# OPENMV3.net
KiCad netlist of a schematic drawn in Altium Designer
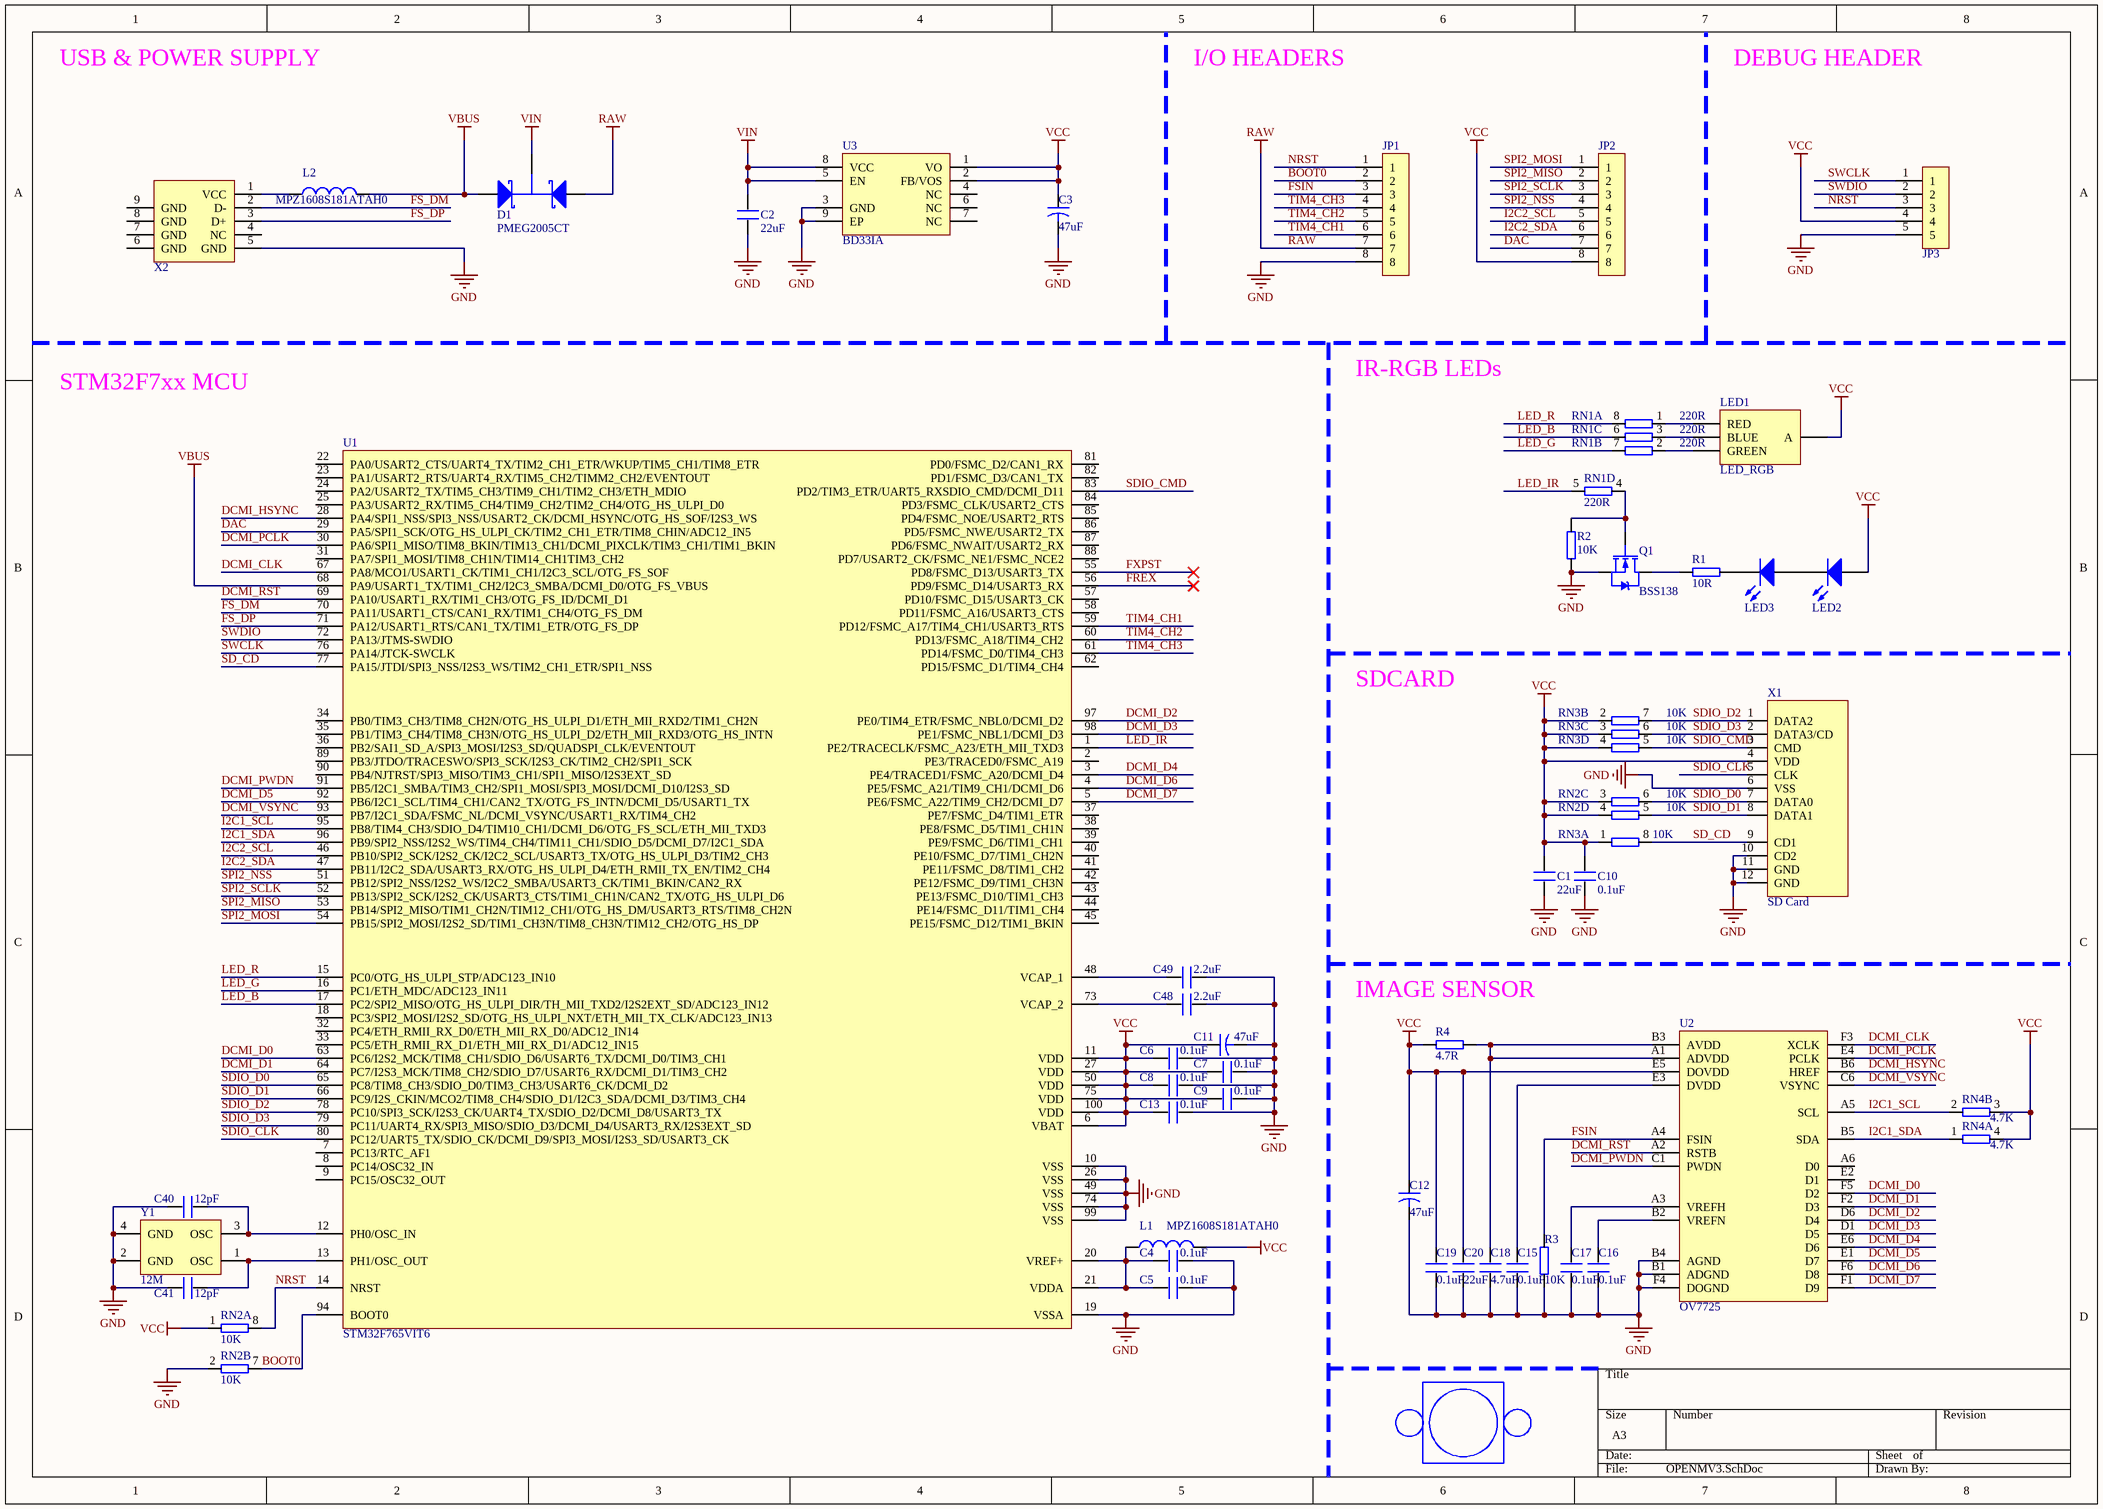
[diagram p0: OPENMV3.SchDoc]

(export (version "E")
  (design (tool "Eeschema 10.0.6"))
  (components
    (comp (ref "C1")
      (value "22uF")
      (footprint "C0603")
      (fields (field (name "Comment") "CAP"))
      (libsource (lib "MyLib") (part "C"))
    )
    (comp (ref "C2")
      (value "22uF")
      (footprint "C0603")
      (fields (field (name "Comment") "CAP"))
      (libsource (lib "MyLib") (part "C"))
    )
    (comp (ref "C3")
      (value "47uF")
      (footprint "CAP-A")
      (fields (field (name "Comment") "CAP"))
      (libsource (lib "MyLib") (part "CAP-B"))
    )
    (comp (ref "C4")
      (value "0.1uF")
      (footprint "C0603")
      (fields (field (name "Comment") "CAP"))
      (libsource (lib "MyLib") (part "C"))
    )
    (comp (ref "C5")
      (value "0.1uF")
      (footprint "C0603")
      (fields (field (name "Comment") "CAP"))
      (libsource (lib "MyLib") (part "C"))
    )
    (comp (ref "C6")
      (value "0.1uF")
      (footprint "C0603")
      (fields (field (name "Comment") "CAP"))
      (libsource (lib "MyLib") (part "C"))
    )
    (comp (ref "C7")
      (value "0.1uF")
      (footprint "C0603")
      (fields (field (name "Comment") "CAP"))
      (libsource (lib "MyLib") (part "C"))
    )
    (comp (ref "C8")
      (value "0.1uF")
      (footprint "C0603")
      (fields (field (name "Comment") "CAP"))
      (libsource (lib "MyLib") (part "C"))
    )
    (comp (ref "C9")
      (value "0.1uF")
      (footprint "C0603")
      (fields (field (name "Comment") "CAP"))
      (libsource (lib "MyLib") (part "C"))
    )
    (comp (ref "C10")
      (value "0.1uF")
      (footprint "C0603")
      (fields (field (name "Comment") "CAP"))
      (libsource (lib "MyLib") (part "C"))
    )
    (comp (ref "C11")
      (value "47uF")
      (footprint "CAP-A")
      (fields (field (name "Comment") "CAP"))
      (libsource (lib "MyLib") (part "CAP-B"))
    )
    (comp (ref "C12")
      (value "47uF")
      (footprint "CAP-A")
      (fields (field (name "Comment") "CAP"))
      (libsource (lib "MyLib") (part "CAP-B"))
    )
    (comp (ref "C13")
      (value "0.1uF")
      (footprint "C0603")
      (fields (field (name "Comment") "CAP"))
      (libsource (lib "MyLib") (part "C"))
    )
    (comp (ref "C15")
      (value "0.1uF")
      (footprint "C0603")
      (fields (field (name "Comment") "CAP"))
      (libsource (lib "MyLib") (part "C"))
    )
    (comp (ref "C16")
      (value "0.1uF")
      (footprint "C0603")
      (fields (field (name "Comment") "CAP"))
      (libsource (lib "MyLib") (part "C"))
    )
    (comp (ref "C17")
      (value "0.1uF")
      (footprint "C0603")
      (fields (field (name "Comment") "CAP"))
      (libsource (lib "MyLib") (part "C"))
    )
    (comp (ref "C18")
      (value "4.7uF")
      (footprint "C0603")
      (fields (field (name "Comment") "CAP"))
      (libsource (lib "MyLib") (part "C"))
    )
    (comp (ref "C19")
      (value "0.1uF")
      (footprint "C0603")
      (fields (field (name "Comment") "CAP"))
      (libsource (lib "MyLib") (part "C"))
    )
    (comp (ref "C20")
      (value "22uF")
      (footprint "C0603")
      (fields (field (name "Comment") "CAP"))
      (libsource (lib "MyLib") (part "C"))
    )
    (comp (ref "C40")
      (value "12pF")
      (footprint "C0603")
      (fields (field (name "Comment") "CAP"))
      (libsource (lib "MyLib") (part "C"))
    )
    (comp (ref "C41")
      (value "12pF")
      (footprint "C0603")
      (fields (field (name "Comment") "CAP"))
      (libsource (lib "MyLib") (part "C"))
    )
    (comp (ref "C48")
      (value "2.2uF")
      (footprint "C0603")
      (fields (field (name "Comment") "CAP"))
      (libsource (lib "MyLib") (part "C"))
    )
    (comp (ref "C49")
      (value "2.2uF")
      (footprint "C0603")
      (fields (field (name "Comment") "CAP"))
      (libsource (lib "MyLib") (part "C"))
    )
    (comp (ref "D1") (value "PMEG2005CT") (footprint "SOT-23") (libsource (lib "MyLib") (part "D_Double")))
    (comp (ref "JP1")
      (value "HEADER1*8")
      (footprint "HEADER1*8_oct")
      (libsource (lib "MyLib") (part "HEADER1*8"))
    )
    (comp (ref "JP2")
      (value "HEADER1*8")
      (footprint "HEADER1*8_oct")
      (libsource (lib "MyLib") (part "HEADER1*8"))
    )
    (comp (ref "JP3")
      (value "HEADER1*5")
      (footprint "HEADER1*5_oct")
      (libsource (lib "MyLib") (part "HEADER1*5"))
    )
    (comp (ref "L1")
      (value "MPZ1608S181ATAH0")
      (footprint "R0603")
      (fields (field (name "Comment") "Inductance"))
      (libsource (lib "MyLib") (part "L"))
    )
    (comp (ref "L2")
      (value "MPZ1608S181ATAH0")
      (footprint "R0603")
      (fields (field (name "Comment") "Inductance"))
      (libsource (lib "MyLib") (part "L"))
    )
    (comp (ref "LED1")
      (value "LED_RGB")
      (footprint "LED_RGB_3528")
      (libsource (lib "MyLib") (part "LED_RGB"))
    )
    (comp (ref "LED2") (value "LED") (footprint "LED1206") (libsource (lib "MyLib") (part "LED")))
    (comp (ref "LED3") (value "LED") (footprint "LED1206") (libsource (lib "MyLib") (part "LED")))
    (comp (ref "P0")
      (value "CameraLens")
      (footprint "CamLens_M12-2016")
      (libsource (lib "MyLib") (part "CameraLens"))
    )
    (comp (ref "Q1") (value "BSS138") (footprint "sot-23") (libsource (lib "MyLib") (part "AO3402")))
    (comp (ref "R1")
      (value "10R")
      (footprint "R0603")
      (fields (field (name "Comment") "Resistor"))
      (libsource (lib "MyLib") (part "R"))
    )
    (comp (ref "R2")
      (value "10K")
      (footprint "R0603")
      (fields (field (name "Comment") "Resistor"))
      (libsource (lib "MyLib") (part "R"))
    )
    (comp (ref "R3")
      (value "10K")
      (footprint "R0603")
      (fields (field (name "Comment") "Resistor"))
      (libsource (lib "MyLib") (part "R"))
    )
    (comp (ref "R4")
      (value "4.7R")
      (footprint "R0603")
      (fields (field (name "Comment") "Resistor"))
      (libsource (lib "MyLib") (part "R"))
    )
    (comp (ref "RN1")
      (value "220R")
      (footprint "R0603_x4")
      (fields (field (name "Comment") "Res"))
      (libsource (lib "MyLib") (part "RES-Pack4"))
    )
    (comp (ref "RN2")
      (value "10K")
      (footprint "R0603_x4")
      (fields (field (name "Comment") "Res"))
      (libsource (lib "MyLib") (part "RES-Pack4"))
    )
    (comp (ref "RN3")
      (value "10K")
      (footprint "R0603_x4")
      (fields (field (name "Comment") "Res"))
      (libsource (lib "MyLib") (part "RES-Pack4"))
    )
    (comp (ref "RN4")
      (value "4.7K")
      (footprint "R0603_x2")
      (fields (field (name "Comment") "Res"))
      (libsource (lib "MyLib") (part "RES-Pack2"))
    )
    (comp (ref "U1")
      (value "STM32F765VIT6")
      (footprint "LQFP100")
      (libsource (lib "MyLib") (part "STM32F765VIT6"))
    )
    (comp (ref "U2")
      (value "OV7725")
      (footprint "BGA28C80P6X6_535X535X96")
      (libsource (lib "MyLib") (part "OV7725"))
    )
    (comp (ref "U3") (value "BD33IA") (footprint "SOIC8-HS") (libsource (lib "MyLib") (part "BD33IA")))
    (comp (ref "X1") (value "SD Card") (footprint "SD_Slot") (libsource (lib "MyLib") (part "SD_Slot")))
    (comp (ref "X2") (value "USB") (footprint "MicroUSB_5P_2h") (libsource (lib "MyLib") (part "USB")))
    (comp (ref "Y1")
      (value "12M")
      (footprint "XTAL-3225")
      (fields (field (name "Comment") "Crystal"))
      (libsource (lib "MyLib") (part "无源晶振"))
    )
  )
  (nets
    (net (code "1") (name "/BOOT0") (class "Default")
      (node (ref "JP1") (pin "2") (pinfunction "2_2") (pintype "passive"))
      (node (ref "RN2") (pin "7") (pintype "passive"))
      (node (ref "U1") (pin "94") (pinfunction "BOOT0_94") (pintype "passive"))
    )
    (net (code "2") (name "/DAC") (class "Default")
      (node (ref "JP2") (pin "7") (pinfunction "7_7") (pintype "passive"))
      (node (ref "U1") (pin "29") (pinfunction "PA5/SPI1_SCK/OTG_HS_ULPI_CK/TIM2_CH1_ETR/TIM8_CHIN/ADC12_IN5_29") (pintype "passive"))
    )
    (net (code "3") (name "/DCMI_CLK") (class "Default")
      (node (ref "U1") (pin "67") (pinfunction "PA8/MCO1/USART1_CK/TIM1_CH1/I2C3_SCL/OTG_FS_SOF_67") (pintype "passive"))
      (node (ref "U2") (pin "F3") (pinfunction "XCLK_F3") (pintype "passive"))
    )
    (net (code "4") (name "/DCMI_D0") (class "Default")
      (node (ref "U1") (pin "63") (pinfunction "PC6/I2S2_MCK/TIM8_CH1/SDIO_D6/USART6_TX/DCMI_D0/TIM3_CH1_63") (pintype "passive"))
      (node (ref "U2") (pin "F5") (pinfunction "D2_F5") (pintype "passive"))
    )
    (net (code "5") (name "/DCMI_D1") (class "Default")
      (node (ref "U1") (pin "64") (pinfunction "PC7/I2S3_MCK/TIM8_CH2/SDIO_D7/USART6_RX/DCMI_D1/TIM3_CH2_64") (pintype "passive"))
      (node (ref "U2") (pin "F2") (pinfunction "D3_F2") (pintype "passive"))
    )
    (net (code "6") (name "/DCMI_D2") (class "Default")
      (node (ref "U1") (pin "97") (pinfunction "PE0/TIM4_ETR/FSMC_NBL0/DCMI_D2_97") (pintype "passive"))
      (node (ref "U2") (pin "D6") (pinfunction "D4_D6") (pintype "passive"))
    )
    (net (code "7") (name "/DCMI_D3") (class "Default")
      (node (ref "U1") (pin "98") (pinfunction "PE1/FSMC_NBL1/DCMI_D3_98") (pintype "passive"))
      (node (ref "U2") (pin "D1") (pinfunction "D5_D1") (pintype "passive"))
    )
    (net (code "8") (name "/DCMI_D4") (class "Default")
      (node (ref "U1") (pin "3") (pinfunction "PE4/TRACED1/FSMC_A20/DCMI_D4_3") (pintype "passive"))
      (node (ref "U2") (pin "E6") (pinfunction "D6_E6") (pintype "passive"))
    )
    (net (code "9") (name "/DCMI_D5") (class "Default")
      (node (ref "U1") (pin "92") (pinfunction "PB6/I2C1_SCL/TIM4_CH1/CAN2_TX/OTG_FS_INTN/DCMI_D5/USART1_TX_92") (pintype "passive"))
      (node (ref "U2") (pin "E1") (pinfunction "D7_E1") (pintype "passive"))
    )
    (net (code "10") (name "/DCMI_D6") (class "Default")
      (node (ref "U1") (pin "4") (pinfunction "PE5/FSMC_A21/TIM9_CH1/DCMI_D6_4") (pintype "passive"))
      (node (ref "U2") (pin "F6") (pinfunction "D8_F6") (pintype "passive"))
    )
    (net (code "11") (name "/DCMI_D7") (class "Default")
      (node (ref "U1") (pin "5") (pinfunction "PE6/FSMC_A22/TIM9_CH2/DCMI_D7_5") (pintype "passive"))
      (node (ref "U2") (pin "F1") (pinfunction "D9_F1") (pintype "passive"))
    )
    (net (code "12") (name "/DCMI_HSYNC") (class "Default")
      (node (ref "U1") (pin "28") (pinfunction "PA4/SPI1_NSS/SPI3_NSS/USART2_CK/DCMI_HSYNC/OTG_HS_SOF/I2S3_WS_28") (pintype "passive"))
      (node (ref "U2") (pin "B6") (pinfunction "HREF_B6") (pintype "passive"))
    )
    (net (code "13") (name "/DCMI_PCLK") (class "Default")
      (node (ref "U1") (pin "30") (pinfunction "PA6/SPI1_MISO/TIM8_BKIN/TIM13_CH1/DCMI_PIXCLK/TIM3_CH1/TIM1_BKIN_30") (pintype "passive"))
      (node (ref "U2") (pin "E4") (pinfunction "PCLK_E4") (pintype "passive"))
    )
    (net (code "14") (name "/DCMI_PWDN") (class "Default")
      (node (ref "U1") (pin "91") (pinfunction "PB5/I2C1_SMBA/TIM3_CH2/SPI1_MOSI/SPI3_MOSI/DCMI_D10/I2S3_SD_91") (pintype "passive"))
      (node (ref "U2") (pin "C1") (pinfunction "PWDN_C1") (pintype "passive"))
    )
    (net (code "15") (name "/DCMI_RST") (class "Default")
      (node (ref "U1") (pin "69") (pinfunction "PA10/USART1_RX/TIM1_CH3/OTG_FS_ID/DCMI_D1_69") (pintype "passive"))
      (node (ref "U2") (pin "A2") (pinfunction "RSTB_A2") (pintype "passive"))
    )
    (net (code "16") (name "/DCMI_VSYNC") (class "Default")
      (node (ref "U1") (pin "93") (pinfunction "PB7/I2C1_SDA/FSMC_NL/DCMI_VSYNC/USART1_RX/TIM4_CH2_93") (pintype "passive"))
      (node (ref "U2") (pin "C6") (pinfunction "VSYNC_C6") (pintype "passive"))
    )
    (net (code "17") (name "/FREX") (class "Default")
      (node (ref "U1") (pin "56") (pinfunction "PD9/FSMC_D14/USART3_RX_56") (pintype "passive+no_connect"))
    )
    (net (code "18") (name "/FSIN") (class "Default")
      (node (ref "JP1") (pin "3") (pinfunction "3_3") (pintype "passive"))
      (node (ref "R3") (pin "2") (pintype "passive"))
      (node (ref "U2") (pin "A4") (pinfunction "FSIN_A4") (pintype "passive"))
    )
    (net (code "19") (name "/FS_DM") (class "Default")
      (node (ref "U1") (pin "70") (pinfunction "PA11/USART1_CTS/CAN1_RX/TIM1_CH4/OTG_FS_DM_70") (pintype "passive"))
      (node (ref "X2") (pin "2") (pinfunction "D-_2") (pintype "passive"))
    )
    (net (code "20") (name "/FS_DP") (class "Default")
      (node (ref "U1") (pin "71") (pinfunction "PA12/USART1_RTS/CAN1_TX/TIM1_ETR/OTG_FS_DP_71") (pintype "passive"))
      (node (ref "X2") (pin "3") (pinfunction "D+_3") (pintype "passive"))
    )
    (net (code "21") (name "/FXPST") (class "Default")
      (node (ref "U1") (pin "55") (pinfunction "PD8/FSMC_D13/USART3_TX_55") (pintype "passive+no_connect"))
    )
    (net (code "22") (name "/I2C1_SCL") (class "Default")
      (node (ref "RN4") (pin "2") (pintype "passive"))
      (node (ref "U1") (pin "95") (pinfunction "PB8/TIM4_CH3/SDIO_D4/TIM10_CH1/DCMI_D6/OTG_FS_SCL/ETH_MII_TXD3_95") (pintype "passive"))
      (node (ref "U2") (pin "A5") (pinfunction "SCL_A5") (pintype "passive"))
    )
    (net (code "23") (name "/I2C1_SDA") (class "Default")
      (node (ref "RN4") (pin "1") (pinfunction "1_1") (pintype "passive"))
      (node (ref "U1") (pin "96") (pinfunction "PB9/SPI2_NSS/I2S2_WS/TIM4_CH4/TIM11_CH1/SDIO_D5/DCMI_D7/I2C1_SDA_96") (pintype "passive"))
      (node (ref "U2") (pin "B5") (pinfunction "SDA_B5") (pintype "passive"))
    )
    (net (code "24") (name "/I2C2_SCL") (class "Default")
      (node (ref "JP2") (pin "5") (pinfunction "5_5") (pintype "passive"))
      (node (ref "U1") (pin "46") (pinfunction "PB10/SPI2_SCK/I2S2_CK/I2C2_SCL/USART3_TX/OTG_HS_ULPI_D3/TIM2_CH3_46") (pintype "passive"))
    )
    (net (code "25") (name "/I2C2_SDA") (class "Default")
      (node (ref "JP2") (pin "6") (pinfunction "6_6") (pintype "passive"))
      (node (ref "U1") (pin "47") (pinfunction "PB11/I2C2_SDA/USART3_RX/OTG_HS_ULPI_D4/ETH_RMII_TX_EN/TIM2_CH4_47") (pintype "passive"))
    )
    (net (code "26") (name "/LED_B") (class "Default")
      (node (ref "RN1") (pin "6") (pintype "passive"))
      (node (ref "U1") (pin "17") (pinfunction "PC2/SPI2_MISO/OTG_HS_ULPI_DIR/TH_MII_TXD2/I2S2EXT_SD/ADC123_IN12_17") (pintype "passive"))
    )
    (net (code "27") (name "/LED_G") (class "Default")
      (node (ref "RN1") (pin "7") (pintype "passive"))
      (node (ref "U1") (pin "16") (pinfunction "PC1/ETH_MDC/ADC123_IN11_16") (pintype "passive"))
    )
    (net (code "28") (name "/LED_IR") (class "Default")
      (node (ref "RN1") (pin "5") (pintype "passive"))
      (node (ref "U1") (pin "1") (pinfunction "PE2/TRACECLK/FSMC_A23/ETH_MII_TXD3_1") (pintype "passive"))
    )
    (net (code "29") (name "/LED_R") (class "Default")
      (node (ref "RN1") (pin "8") (pinfunction "8_8") (pintype "passive"))
      (node (ref "U1") (pin "15") (pinfunction "PC0/OTG_HS_ULPI_STP/ADC123_IN10_15") (pintype "passive"))
    )
    (net (code "30") (name "/NRST") (class "Default")
      (node (ref "JP1") (pin "1") (pinfunction "1_1") (pintype "passive"))
      (node (ref "JP3") (pin "3") (pinfunction "3_3") (pintype "passive"))
      (node (ref "RN2") (pin "8") (pinfunction "8_8") (pintype "passive"))
      (node (ref "U1") (pin "14") (pinfunction "NRST_14") (pintype "passive"))
    )
    (net (code "31") (name "/SDIO_CLK") (class "Default")
      (node (ref "U1") (pin "80") (pinfunction "PC12/UART5_TX/SDIO_CK/DCMI_D9/SPI3_MOSI/I2S3_SD/USART3_CK_80") (pintype "passive"))
      (node (ref "X1") (pin "5") (pinfunction "CLK_5") (pintype "passive"))
    )
    (net (code "32") (name "/SDIO_CMD") (class "Default")
      (node (ref "RN3") (pin "5") (pintype "passive"))
      (node (ref "U1") (pin "83") (pinfunction "PD2/TIM3_ETR/UART5_RXSDIO_CMD/DCMI_D11_83") (pintype "passive"))
      (node (ref "X1") (pin "3") (pinfunction "CMD_3") (pintype "passive"))
    )
    (net (code "33") (name "/SDIO_D0") (class "Default")
      (node (ref "RN2") (pin "6") (pintype "passive"))
      (node (ref "U1") (pin "65") (pinfunction "PC8/TIM8_CH3/SDIO_D0/TIM3_CH3/USART6_CK/DCMI_D2_65") (pintype "passive"))
      (node (ref "X1") (pin "7") (pinfunction "DATA0_7") (pintype "passive"))
    )
    (net (code "34") (name "/SDIO_D1") (class "Default")
      (node (ref "RN2") (pin "5") (pintype "passive"))
      (node (ref "U1") (pin "66") (pinfunction "PC9/I2S_CKIN/MCO2/TIM8_CH4/SDIO_D1/I2C3_SDA/DCMI_D3/TIM3_CH4_66") (pintype "passive"))
      (node (ref "X1") (pin "8") (pinfunction "DATA1_8") (pintype "passive"))
    )
    (net (code "35") (name "/SDIO_D2") (class "Default")
      (node (ref "RN3") (pin "7") (pintype "passive"))
      (node (ref "U1") (pin "78") (pinfunction "PC10/SPI3_SCK/I2S3_CK/UART4_TX/SDIO_D2/DCMI_D8/USART3_TX_78") (pintype "passive"))
      (node (ref "X1") (pin "1") (pinfunction "DATA2_1") (pintype "passive"))
    )
    (net (code "36") (name "/SDIO_D3") (class "Default")
      (node (ref "RN3") (pin "6") (pintype "passive"))
      (node (ref "U1") (pin "79") (pinfunction "PC11/UART4_RX/SPI3_MISO/SDIO_D3/DCMI_D4/USART3_RX/I2S3EXT_SD_79") (pintype "passive"))
      (node (ref "X1") (pin "2") (pinfunction "DATA3/CD_2") (pintype "passive"))
    )
    (net (code "37") (name "/SD_CD") (class "Default")
      (node (ref "RN3") (pin "8") (pinfunction "8_8") (pintype "passive"))
      (node (ref "U1") (pin "77") (pinfunction "PA15/JTDI/SPI3_NSS/I2S3_WS/TIM2_CH1_ETR/SPI1_NSS_77") (pintype "passive"))
      (node (ref "X1") (pin "9") (pinfunction "CD1_9") (pintype "passive"))
    )
    (net (code "38") (name "/SPI2_MISO") (class "Default")
      (node (ref "JP2") (pin "2") (pinfunction "2_2") (pintype "passive"))
      (node (ref "U1") (pin "53") (pinfunction "PB14/SPI2_MISO/TIM1_CH2N/TIM12_CH1/OTG_HS_DM/USART3_RTS/TIM8_CH2N_53") (pintype "passive"))
    )
    (net (code "39") (name "/SPI2_MOSI") (class "Default")
      (node (ref "JP2") (pin "1") (pinfunction "1_1") (pintype "passive"))
      (node (ref "U1") (pin "54") (pinfunction "PB15/SPI2_MOSI/I2S2_SD/TIM1_CH3N/TIM8_CH3N/TIM12_CH2/OTG_HS_DP_54") (pintype "passive"))
    )
    (net (code "40") (name "/SPI2_NSS") (class "Default")
      (node (ref "JP2") (pin "4") (pinfunction "4_4") (pintype "passive"))
      (node (ref "U1") (pin "51") (pinfunction "PB12/SPI2_NSS/I2S2_WS/I2C2_SMBA/USART3_CK/TIM1_BKIN/CAN2_RX_51") (pintype "passive"))
    )
    (net (code "41") (name "/SPI2_SCLK") (class "Default")
      (node (ref "JP2") (pin "3") (pinfunction "3_3") (pintype "passive"))
      (node (ref "U1") (pin "52") (pinfunction "PB13/SPI2_SCK/I2S2_CK/USART3_CTS/TIM1_CH1N/CAN2_TX/OTG_HS_ULPI_D6_52") (pintype "passive"))
    )
    (net (code "42") (name "/SWCLK") (class "Default")
      (node (ref "JP3") (pin "1") (pinfunction "1_1") (pintype "passive"))
      (node (ref "U1") (pin "76") (pinfunction "PA14/JTCK-SWCLK_76") (pintype "passive"))
    )
    (net (code "43") (name "/SWDIO") (class "Default")
      (node (ref "JP3") (pin "2") (pinfunction "2_2") (pintype "passive"))
      (node (ref "U1") (pin "72") (pinfunction "PA13/JTMS-SWDIO_72") (pintype "passive"))
    )
    (net (code "44") (name "/TIM4_CH1") (class "Default")
      (node (ref "JP1") (pin "6") (pinfunction "6_6") (pintype "passive"))
      (node (ref "U1") (pin "59") (pinfunction "PD12/FSMC_A17/TIM4_CH1/USART3_RTS_59") (pintype "passive"))
    )
    (net (code "45") (name "/TIM4_CH2") (class "Default")
      (node (ref "JP1") (pin "5") (pinfunction "5_5") (pintype "passive"))
      (node (ref "U1") (pin "60") (pinfunction "PD13/FSMC_A18/TIM4_CH2_60") (pintype "passive"))
    )
    (net (code "46") (name "/TIM4_CH3") (class "Default")
      (node (ref "JP1") (pin "4") (pinfunction "4_4") (pintype "passive"))
      (node (ref "U1") (pin "61") (pinfunction "PD14/FSMC_D0/TIM4_CH3_61") (pintype "passive"))
    )
    (net (code "47") (name "GND") (class "Default")
      (node (ref "C1") (pin "1") (pintype "passive"))
      (node (ref "C10") (pin "1") (pintype "passive"))
      (node (ref "C11") (pin "1") (pinfunction "1_1") (pintype "passive"))
      (node (ref "C12") (pin "1") (pinfunction "1_1") (pintype "passive"))
      (node (ref "C13") (pin "2") (pintype "passive"))
      (node (ref "C15") (pin "1") (pintype "passive"))
      (node (ref "C16") (pin "1") (pintype "passive"))
      (node (ref "C17") (pin "1") (pintype "passive"))
      (node (ref "C18") (pin "1") (pintype "passive"))
      (node (ref "C19") (pin "1") (pintype "passive"))
      (node (ref "C2") (pin "1") (pintype "passive"))
      (node (ref "C20") (pin "1") (pintype "passive"))
      (node (ref "C3") (pin "1") (pinfunction "1_1") (pintype "passive"))
      (node (ref "C4") (pin "2") (pintype "passive"))
      (node (ref "C40") (pin "2") (pintype "passive"))
      (node (ref "C41") (pin "2") (pintype "passive"))
      (node (ref "C48") (pin "1") (pintype "passive"))
      (node (ref "C49") (pin "1") (pintype "passive"))
      (node (ref "C5") (pin "2") (pintype "passive"))
      (node (ref "C6") (pin "2") (pintype "passive"))
      (node (ref "C7") (pin "2") (pintype "passive"))
      (node (ref "C8") (pin "2") (pintype "passive"))
      (node (ref "C9") (pin "2") (pintype "passive"))
      (node (ref "JP1") (pin "8") (pinfunction "8_8") (pintype "passive"))
      (node (ref "JP3") (pin "5") (pinfunction "5_5") (pintype "passive"))
      (node (ref "Q1") (pin "2") (pinfunction "S_2") (pintype "passive"))
      (node (ref "R2") (pin "1") (pintype "passive"))
      (node (ref "R3") (pin "1") (pintype "passive"))
      (node (ref "RN2") (pin "2") (pintype "passive"))
      (node (ref "U1") (pin "10") (pinfunction "VSS_10") (pintype "passive"))
      (node (ref "U1") (pin "19") (pinfunction "VSSA_19") (pintype "passive"))
      (node (ref "U1") (pin "26") (pinfunction "VSS_26") (pintype "passive"))
      (node (ref "U1") (pin "49") (pinfunction "VSS_49") (pintype "passive"))
      (node (ref "U1") (pin "74") (pinfunction "VSS_74") (pintype "passive"))
      (node (ref "U1") (pin "99") (pinfunction "VSS_99") (pintype "passive"))
      (node (ref "U2") (pin "B1") (pinfunction "ADGND_B1") (pintype "passive"))
      (node (ref "U2") (pin "B4") (pinfunction "AGND_B4") (pintype "passive"))
      (node (ref "U2") (pin "F4") (pinfunction "DOGND_F4") (pintype "passive"))
      (node (ref "U3") (pin "3") (pinfunction "GND_3") (pintype "passive"))
      (node (ref "U3") (pin "9") (pinfunction "EP_9") (pintype "passive"))
      (node (ref "X1") (pin "10") (pinfunction "CD2_10") (pintype "passive"))
      (node (ref "X1") (pin "11") (pinfunction "GND_11") (pintype "passive"))
      (node (ref "X1") (pin "12") (pinfunction "GND_12") (pintype "passive"))
      (node (ref "X1") (pin "6") (pinfunction "VSS_6") (pintype "passive"))
      (node (ref "X2") (pin "5") (pinfunction "GND_5") (pintype "passive"))
      (node (ref "Y1") (pin "2") (pinfunction "GND_2") (pintype "passive"))
      (node (ref "Y1") (pin "4") (pinfunction "GND_4") (pintype "passive"))
    )
    (net (code "48") (name "Net-(LED1-BLUE)") (class "Default")
      (node (ref "LED1") (pin "3") (pinfunction "BLUE_3") (pintype "passive"))
      (node (ref "RN1") (pin "3") (pintype "passive"))
    )
    (net (code "49") (name "Net-(LED1-GREEN)") (class "Default")
      (node (ref "LED1") (pin "4") (pinfunction "GREEN_4") (pintype "passive"))
      (node (ref "RN1") (pin "2") (pintype "passive"))
    )
    (net (code "50") (name "Net-(LED1-RED)") (class "Default")
      (node (ref "LED1") (pin "1") (pinfunction "RED_1") (pintype "passive"))
      (node (ref "RN1") (pin "1") (pinfunction "1_1") (pintype "passive"))
    )
    (net (code "51") (name "Net-(LED2-K)") (class "Default")
      (node (ref "LED2") (pin "2") (pinfunction "K_2") (pintype "passive"))
      (node (ref "LED3") (pin "1") (pinfunction "A_1") (pintype "passive"))
    )
    (net (code "52") (name "Net-(LED3-K)") (class "Default")
      (node (ref "LED3") (pin "2") (pinfunction "K_2") (pintype "passive"))
      (node (ref "R1") (pin "1") (pintype "passive"))
    )
    (net (code "53") (name "Net-(Q1-D)") (class "Default")
      (node (ref "Q1") (pin "3") (pinfunction "D_3") (pintype "passive"))
      (node (ref "R1") (pin "2") (pintype "passive"))
    )
    (net (code "54") (name "Net-(Q1-G)") (class "Default")
      (node (ref "Q1") (pin "1") (pinfunction "G_1") (pintype "passive"))
      (node (ref "R2") (pin "2") (pintype "passive"))
      (node (ref "RN1") (pin "4") (pintype "passive"))
    )
    (net (code "55") (name "Net-(U1-PH0{slash}OSC_IN)") (class "Default")
      (node (ref "C40") (pin "1") (pintype "passive"))
      (node (ref "U1") (pin "12") (pinfunction "PH0/OSC_IN_12") (pintype "passive"))
      (node (ref "Y1") (pin "3") (pinfunction "OSC_3") (pintype "passive"))
    )
    (net (code "56") (name "Net-(U1-PH1{slash}OSC_OUT)") (class "Default")
      (node (ref "C41") (pin "1") (pintype "passive"))
      (node (ref "U1") (pin "13") (pinfunction "PH1/OSC_OUT_13") (pintype "passive"))
      (node (ref "Y1") (pin "1") (pinfunction "OSC_1") (pintype "passive"))
    )
    (net (code "57") (name "Net-(U1-VCAP_1)") (class "Default")
      (node (ref "C49") (pin "2") (pintype "passive"))
      (node (ref "U1") (pin "48") (pinfunction "VCAP_1_48") (pintype "passive"))
    )
    (net (code "58") (name "Net-(U1-VCAP_2)") (class "Default")
      (node (ref "C48") (pin "2") (pintype "passive"))
      (node (ref "U1") (pin "73") (pinfunction "VCAP_2_73") (pintype "passive"))
    )
    (net (code "59") (name "Net-(U1-VDDA)") (class "Default")
      (node (ref "C4") (pin "1") (pintype "passive"))
      (node (ref "C5") (pin "1") (pintype "passive"))
      (node (ref "L1") (pin "1") (pinfunction "1_1") (pintype "passive"))
      (node (ref "U1") (pin "20") (pinfunction "VREF+_20") (pintype "passive"))
      (node (ref "U1") (pin "21") (pinfunction "VDDA_21") (pintype "passive"))
    )
    (net (code "60") (name "Net-(U2-ADVDD)") (class "Default")
      (node (ref "C18") (pin "2") (pintype "passive"))
      (node (ref "R4") (pin "1") (pintype "passive"))
      (node (ref "U2") (pin "A1") (pinfunction "ADVDD_A1") (pintype "passive"))
      (node (ref "U2") (pin "B3") (pinfunction "AVDD_B3") (pintype "passive"))
    )
    (net (code "61") (name "Net-(U2-DVDD)") (class "Default")
      (node (ref "C15") (pin "2") (pintype "passive"))
      (node (ref "U2") (pin "E3") (pinfunction "DVDD_E3") (pintype "passive"))
    )
    (net (code "62") (name "Net-(U2-VREFH)") (class "Default")
      (node (ref "C17") (pin "2") (pintype "passive"))
      (node (ref "U2") (pin "A3") (pinfunction "VREFH_A3") (pintype "passive"))
    )
    (net (code "63") (name "Net-(U2-VREFN)") (class "Default")
      (node (ref "C16") (pin "2") (pintype "passive"))
      (node (ref "U2") (pin "B2") (pinfunction "VREFN_B2") (pintype "passive"))
    )
    (net (code "64") (name "Net-(X2-VCC)") (class "Default")
      (node (ref "L2") (pin "1") (pinfunction "1_1") (pintype "passive"))
      (node (ref "X2") (pin "1") (pinfunction "VCC_1") (pintype "passive"))
    )
    (net (code "65") (name "RAW") (class "Default")
      (node (ref "D1") (pin "1") (pinfunction "1_1") (pintype "passive"))
      (node (ref "JP1") (pin "7") (pinfunction "7_7") (pintype "passive"))
    )
    (net (code "66") (name "VBUS") (class "Default")
      (node (ref "D1") (pin "2") (pinfunction "2_2") (pintype "passive"))
      (node (ref "L2") (pin "2") (pinfunction "2_2") (pintype "passive"))
      (node (ref "U1") (pin "68") (pinfunction "PA9/USART1_TX/TIM1_CH2/I2C3_SMBA/DCMI_D0/OTG_FS_VBUS_68") (pintype "passive"))
    )
    (net (code "67") (name "VCC") (class "Default")
      (node (ref "C1") (pin "2") (pintype "passive"))
      (node (ref "C10") (pin "2") (pintype "passive"))
      (node (ref "C11") (pin "2") (pinfunction "2_2") (pintype "passive"))
      (node (ref "C12") (pin "2") (pinfunction "2_2") (pintype "passive"))
      (node (ref "C13") (pin "1") (pintype "passive"))
      (node (ref "C19") (pin "2") (pintype "passive"))
      (node (ref "C20") (pin "2") (pintype "passive"))
      (node (ref "C3") (pin "2") (pinfunction "2_2") (pintype "passive"))
      (node (ref "C6") (pin "1") (pintype "passive"))
      (node (ref "C7") (pin "1") (pintype "passive"))
      (node (ref "C8") (pin "1") (pintype "passive"))
      (node (ref "C9") (pin "1") (pintype "passive"))
      (node (ref "JP2") (pin "8") (pinfunction "8_8") (pintype "passive"))
      (node (ref "JP3") (pin "4") (pinfunction "4_4") (pintype "passive"))
      (node (ref "L1") (pin "2") (pinfunction "2_2") (pintype "passive"))
      (node (ref "LED1") (pin "2") (pinfunction "A_2") (pintype "passive"))
      (node (ref "LED2") (pin "1") (pinfunction "A_1") (pintype "passive"))
      (node (ref "R4") (pin "2") (pintype "passive"))
      (node (ref "RN2") (pin "1") (pinfunction "1_1") (pintype "passive"))
      (node (ref "RN2") (pin "3") (pintype "passive"))
      (node (ref "RN2") (pin "4") (pintype "passive"))
      (node (ref "RN3") (pin "1") (pinfunction "1_1") (pintype "passive"))
      (node (ref "RN3") (pin "2") (pintype "passive"))
      (node (ref "RN3") (pin "3") (pintype "passive"))
      (node (ref "RN3") (pin "4") (pintype "passive"))
      (node (ref "RN4") (pin "3") (pintype "passive"))
      (node (ref "RN4") (pin "4") (pinfunction "4_4") (pintype "passive"))
      (node (ref "U1") (pin "100") (pinfunction "VDD_100") (pintype "passive"))
      (node (ref "U1") (pin "11") (pinfunction "VDD_11") (pintype "passive"))
      (node (ref "U1") (pin "27") (pinfunction "VDD_27") (pintype "passive"))
      (node (ref "U1") (pin "50") (pinfunction "VDD_50") (pintype "passive"))
      (node (ref "U1") (pin "6") (pinfunction "VBAT_6") (pintype "passive"))
      (node (ref "U1") (pin "75") (pinfunction "VDD_75") (pintype "passive"))
      (node (ref "U2") (pin "E5") (pinfunction "DOVDD_E5") (pintype "passive"))
      (node (ref "U3") (pin "1") (pinfunction "VO_1") (pintype "passive"))
      (node (ref "U3") (pin "2") (pinfunction "FB/VOS_2") (pintype "passive"))
      (node (ref "X1") (pin "4") (pinfunction "VDD_4") (pintype "passive"))
    )
    (net (code "68") (name "VIN") (class "Default")
      (node (ref "C2") (pin "2") (pintype "passive"))
      (node (ref "D1") (pin "3") (pinfunction "3_3") (pintype "passive"))
      (node (ref "U3") (pin "5") (pinfunction "EN_5") (pintype "passive"))
      (node (ref "U3") (pin "8") (pinfunction "VCC_8") (pintype "passive"))
    )
    (net (code "69") (name "unconnected-(U1-PA0{slash}USART2_CTS{slash}UART4_TX{slash}TIM2_CH1_ETR{slash}WKUP{slash}TIM5_CH1{slash}TIM8_ETR-Pad22)") (class "Default")
      (node (ref "U1") (pin "22") (pinfunction "PA0/USART2_CTS/UART4_TX/TIM2_CH1_ETR/WKUP/TIM5_CH1/TIM8_ETR_22") (pintype "passive"))
    )
    (net (code "70") (name "unconnected-(U1-PA1{slash}USART2_RTS{slash}UART4_RX{slash}TIM5_CH2{slash}TIMM2_CH2{slash}EVENTOUT-Pad23)") (class "Default")
      (node (ref "U1") (pin "23") (pinfunction "PA1/USART2_RTS/UART4_RX/TIM5_CH2/TIMM2_CH2/EVENTOUT_23") (pintype "passive"))
    )
    (net (code "71") (name "unconnected-(U1-PA2{slash}USART2_TX{slash}TIM5_CH3{slash}TIM9_CH1{slash}TIM2_CH3{slash}ETH_MDIO-Pad24)") (class "Default")
      (node (ref "U1") (pin "24") (pinfunction "PA2/USART2_TX/TIM5_CH3/TIM9_CH1/TIM2_CH3/ETH_MDIO_24") (pintype "passive"))
    )
    (net (code "72") (name "unconnected-(U1-PA3{slash}USART2_RX{slash}TIM5_CH4{slash}TIM9_CH2{slash}TIM2_CH4{slash}OTG_HS_ULPI_D0-Pad25)") (class "Default")
      (node (ref "U1") (pin "25") (pinfunction "PA3/USART2_RX/TIM5_CH4/TIM9_CH2/TIM2_CH4/OTG_HS_ULPI_D0_25") (pintype "passive"))
    )
    (net (code "73") (name "unconnected-(U1-PA7{slash}SPI1_MOSI{slash}TIM8_CH1N{slash}TIM14_CH1TIM3_CH2-Pad31)") (class "Default")
      (node (ref "U1") (pin "31") (pinfunction "PA7/SPI1_MOSI/TIM8_CH1N/TIM14_CH1TIM3_CH2_31") (pintype "passive"))
    )
    (net (code "74") (name "unconnected-(U1-PB0{slash}TIM3_CH3{slash}TIM8_CH2N{slash}OTG_HS_ULPI_D1{slash}ETH_MII_RXD2{slash}TIM1_CH2N-Pad34)") (class "Default")
      (node (ref "U1") (pin "34") (pinfunction "PB0/TIM3_CH3/TIM8_CH2N/OTG_HS_ULPI_D1/ETH_MII_RXD2/TIM1_CH2N_34") (pintype "passive"))
    )
    (net (code "75") (name "unconnected-(U1-PB1{slash}TIM3_CH4{slash}TIM8_CH3N{slash}OTG_HS_ULPI_D2{slash}ETH_MII_RXD3{slash}OTG_HS_INTN-Pad35)") (class "Default")
      (node (ref "U1") (pin "35") (pinfunction "PB1/TIM3_CH4/TIM8_CH3N/OTG_HS_ULPI_D2/ETH_MII_RXD3/OTG_HS_INTN_35") (pintype "passive"))
    )
    (net (code "76") (name "unconnected-(U1-PB2{slash}SAI1_SD_A{slash}SPI3_MOSI{slash}I2S3_SD{slash}QUADSPI_CLK{slash}EVENTOUT-Pad36)") (class "Default")
      (node (ref "U1") (pin "36") (pinfunction "PB2/SAI1_SD_A/SPI3_MOSI/I2S3_SD/QUADSPI_CLK/EVENTOUT_36") (pintype "passive"))
    )
    (net (code "77") (name "unconnected-(U1-PB3{slash}JTDO{slash}TRACESWO{slash}SPI3_SCK{slash}I2S3_CK{slash}TIM2_CH2{slash}SPI1_SCK-Pad89)") (class "Default")
      (node (ref "U1") (pin "89") (pinfunction "PB3/JTDO/TRACESWO/SPI3_SCK/I2S3_CK/TIM2_CH2/SPI1_SCK_89") (pintype "passive"))
    )
    (net (code "78") (name "unconnected-(U1-PB4{slash}NJTRST{slash}SPI3_MISO{slash}TIM3_CH1{slash}SPI1_MISO{slash}I2S3EXT_SD-Pad90)") (class "Default")
      (node (ref "U1") (pin "90") (pinfunction "PB4/NJTRST/SPI3_MISO/TIM3_CH1/SPI1_MISO/I2S3EXT_SD_90") (pintype "passive"))
    )
    (net (code "79") (name "unconnected-(U1-PC3{slash}SPI2_MOSI{slash}I2S2_SD{slash}OTG_HS_ULPI_NXT{slash}ETH_MII_TX_CLK{slash}ADC123_IN13-Pad18)") (class "Default")
      (node (ref "U1") (pin "18") (pinfunction "PC3/SPI2_MOSI/I2S2_SD/OTG_HS_ULPI_NXT/ETH_MII_TX_CLK/ADC123_IN13_18") (pintype "passive"))
    )
    (net (code "80") (name "unconnected-(U1-PC4{slash}ETH_RMII_RX_D0{slash}ETH_MII_RX_D0{slash}ADC12_IN14-Pad32)") (class "Default")
      (node (ref "U1") (pin "32") (pinfunction "PC4/ETH_RMII_RX_D0/ETH_MII_RX_D0/ADC12_IN14_32") (pintype "passive"))
    )
    (net (code "81") (name "unconnected-(U1-PC5{slash}ETH_RMII_RX_D1{slash}ETH_MII_RX_D1{slash}ADC12_IN15-Pad33)") (class "Default")
      (node (ref "U1") (pin "33") (pinfunction "PC5/ETH_RMII_RX_D1/ETH_MII_RX_D1/ADC12_IN15_33") (pintype "passive"))
    )
    (net (code "82") (name "unconnected-(U1-PC13{slash}RTC_AF1-Pad7)") (class "Default")
      (node (ref "U1") (pin "7") (pinfunction "PC13/RTC_AF1_7") (pintype "passive"))
    )
    (net (code "83") (name "unconnected-(U1-PC14{slash}OSC32_IN-Pad8)") (class "Default")
      (node (ref "U1") (pin "8") (pinfunction "PC14/OSC32_IN_8") (pintype "passive"))
    )
    (net (code "84") (name "unconnected-(U1-PC15{slash}OSC32_OUT-Pad9)") (class "Default")
      (node (ref "U1") (pin "9") (pinfunction "PC15/OSC32_OUT_9") (pintype "passive"))
    )
    (net (code "85") (name "unconnected-(U1-PD0{slash}FSMC_D2{slash}CAN1_RX-Pad81)") (class "Default")
      (node (ref "U1") (pin "81") (pinfunction "PD0/FSMC_D2/CAN1_RX_81") (pintype "passive"))
    )
    (net (code "86") (name "unconnected-(U1-PD1{slash}FSMC_D3{slash}CAN1_TX-Pad82)") (class "Default")
      (node (ref "U1") (pin "82") (pinfunction "PD1/FSMC_D3/CAN1_TX_82") (pintype "passive"))
    )
    (net (code "87") (name "unconnected-(U1-PD3{slash}FSMC_CLK{slash}USART2_CTS-Pad84)") (class "Default")
      (node (ref "U1") (pin "84") (pinfunction "PD3/FSMC_CLK/USART2_CTS_84") (pintype "passive"))
    )
    (net (code "88") (name "unconnected-(U1-PD4{slash}FSMC_NOE{slash}USART2_RTS-Pad85)") (class "Default")
      (node (ref "U1") (pin "85") (pinfunction "PD4/FSMC_NOE/USART2_RTS_85") (pintype "passive"))
    )
    (net (code "89") (name "unconnected-(U1-PD5{slash}FSMC_NWE{slash}USART2_TX-Pad86)") (class "Default")
      (node (ref "U1") (pin "86") (pinfunction "PD5/FSMC_NWE/USART2_TX_86") (pintype "passive"))
    )
    (net (code "90") (name "unconnected-(U1-PD6{slash}FSMC_NWAIT{slash}USART2_RX-Pad87)") (class "Default")
      (node (ref "U1") (pin "87") (pinfunction "PD6/FSMC_NWAIT/USART2_RX_87") (pintype "passive"))
    )
    (net (code "91") (name "unconnected-(U1-PD7{slash}USART2_CK{slash}FSMC_NE1{slash}FSMC_NCE2-Pad88)") (class "Default")
      (node (ref "U1") (pin "88") (pinfunction "PD7/USART2_CK/FSMC_NE1/FSMC_NCE2_88") (pintype "passive"))
    )
    (net (code "92") (name "unconnected-(U1-PD10{slash}FSMC_D15{slash}USART3_CK-Pad57)") (class "Default")
      (node (ref "U1") (pin "57") (pinfunction "PD10/FSMC_D15/USART3_CK_57") (pintype "passive"))
    )
    (net (code "93") (name "unconnected-(U1-PD11{slash}FSMC_A16{slash}USART3_CTS-Pad58)") (class "Default")
      (node (ref "U1") (pin "58") (pinfunction "PD11/FSMC_A16/USART3_CTS_58") (pintype "passive"))
    )
    (net (code "94") (name "unconnected-(U1-PD15{slash}FSMC_D1{slash}TIM4_CH4-Pad62)") (class "Default")
      (node (ref "U1") (pin "62") (pinfunction "PD15/FSMC_D1/TIM4_CH4_62") (pintype "passive"))
    )
    (net (code "95") (name "unconnected-(U1-PE3{slash}TRACED0{slash}FSMC_A19-Pad2)") (class "Default")
      (node (ref "U1") (pin "2") (pinfunction "PE3/TRACED0/FSMC_A19_2") (pintype "passive"))
    )
    (net (code "96") (name "unconnected-(U1-PE7{slash}FSMC_D4{slash}TIM1_ETR-Pad37)") (class "Default")
      (node (ref "U1") (pin "37") (pinfunction "PE7/FSMC_D4/TIM1_ETR_37") (pintype "passive"))
    )
    (net (code "97") (name "unconnected-(U1-PE8{slash}FSMC_D5{slash}TIM1_CH1N-Pad38)") (class "Default")
      (node (ref "U1") (pin "38") (pinfunction "PE8/FSMC_D5/TIM1_CH1N_38") (pintype "passive"))
    )
    (net (code "98") (name "unconnected-(U1-PE9{slash}FSMC_D6{slash}TIM1_CH1-Pad39)") (class "Default")
      (node (ref "U1") (pin "39") (pinfunction "PE9/FSMC_D6/TIM1_CH1_39") (pintype "passive"))
    )
    (net (code "99") (name "unconnected-(U1-PE10{slash}FSMC_D7{slash}TIM1_CH2N-Pad40)") (class "Default")
      (node (ref "U1") (pin "40") (pinfunction "PE10/FSMC_D7/TIM1_CH2N_40") (pintype "passive"))
    )
    (net (code "100") (name "unconnected-(U1-PE11{slash}FSMC_D8{slash}TIM1_CH2-Pad41)") (class "Default")
      (node (ref "U1") (pin "41") (pinfunction "PE11/FSMC_D8/TIM1_CH2_41") (pintype "passive"))
    )
    (net (code "101") (name "unconnected-(U1-PE12{slash}FSMC_D9{slash}TIM1_CH3N-Pad42)") (class "Default")
      (node (ref "U1") (pin "42") (pinfunction "PE12/FSMC_D9/TIM1_CH3N_42") (pintype "passive"))
    )
    (net (code "102") (name "unconnected-(U1-PE13{slash}FSMC_D10{slash}TIM1_CH3-Pad43)") (class "Default")
      (node (ref "U1") (pin "43") (pinfunction "PE13/FSMC_D10/TIM1_CH3_43") (pintype "passive"))
    )
    (net (code "103") (name "unconnected-(U1-PE14{slash}FSMC_D11{slash}TIM1_CH4-Pad44)") (class "Default")
      (node (ref "U1") (pin "44") (pinfunction "PE14/FSMC_D11/TIM1_CH4_44") (pintype "passive"))
    )
    (net (code "104") (name "unconnected-(U1-PE15{slash}FSMC_D12{slash}TIM1_BKIN-Pad45)") (class "Default")
      (node (ref "U1") (pin "45") (pinfunction "PE15/FSMC_D12/TIM1_BKIN_45") (pintype "passive"))
    )
    (net (code "105") (name "unconnected-(U2-D0-PadA6)") (class "Default")
      (node (ref "U2") (pin "A6") (pinfunction "D0_A6") (pintype "passive"))
    )
    (net (code "106") (name "unconnected-(U2-D1-PadE2)") (class "Default")
      (node (ref "U2") (pin "E2") (pinfunction "D1_E2") (pintype "passive"))
    )
    (net (code "107") (name "unconnected-(U3-NC-Pad4)") (class "Default")
      (node (ref "U3") (pin "4") (pinfunction "NC_4") (pintype "passive"))
    )
    (net (code "108") (name "unconnected-(U3-NC-Pad6)") (class "Default")
      (node (ref "U3") (pin "6") (pinfunction "NC_6") (pintype "passive"))
    )
    (net (code "109") (name "unconnected-(U3-NC-Pad7)") (class "Default")
      (node (ref "U3") (pin "7") (pinfunction "NC_7") (pintype "passive"))
    )
    (net (code "110") (name "unconnected-(X2-GND-Pad6)") (class "Default")
      (node (ref "X2") (pin "6") (pinfunction "GND_6") (pintype "passive"))
    )
    (net (code "111") (name "unconnected-(X2-GND-Pad7)") (class "Default")
      (node (ref "X2") (pin "7") (pinfunction "GND_7") (pintype "passive"))
    )
    (net (code "112") (name "unconnected-(X2-GND-Pad8)") (class "Default")
      (node (ref "X2") (pin "8") (pinfunction "GND_8") (pintype "passive"))
    )
    (net (code "113") (name "unconnected-(X2-GND-Pad9)") (class "Default")
      (node (ref "X2") (pin "9") (pinfunction "GND_9") (pintype "passive"))
    )
    (net (code "114") (name "unconnected-(X2-NC-Pad4)") (class "Default")
      (node (ref "X2") (pin "4") (pinfunction "NC_4") (pintype "passive"))
    )
  )
)
